# univ_3-1-0-x-rev1.net
KiCad netlist of a schematic drawn in EAGLE
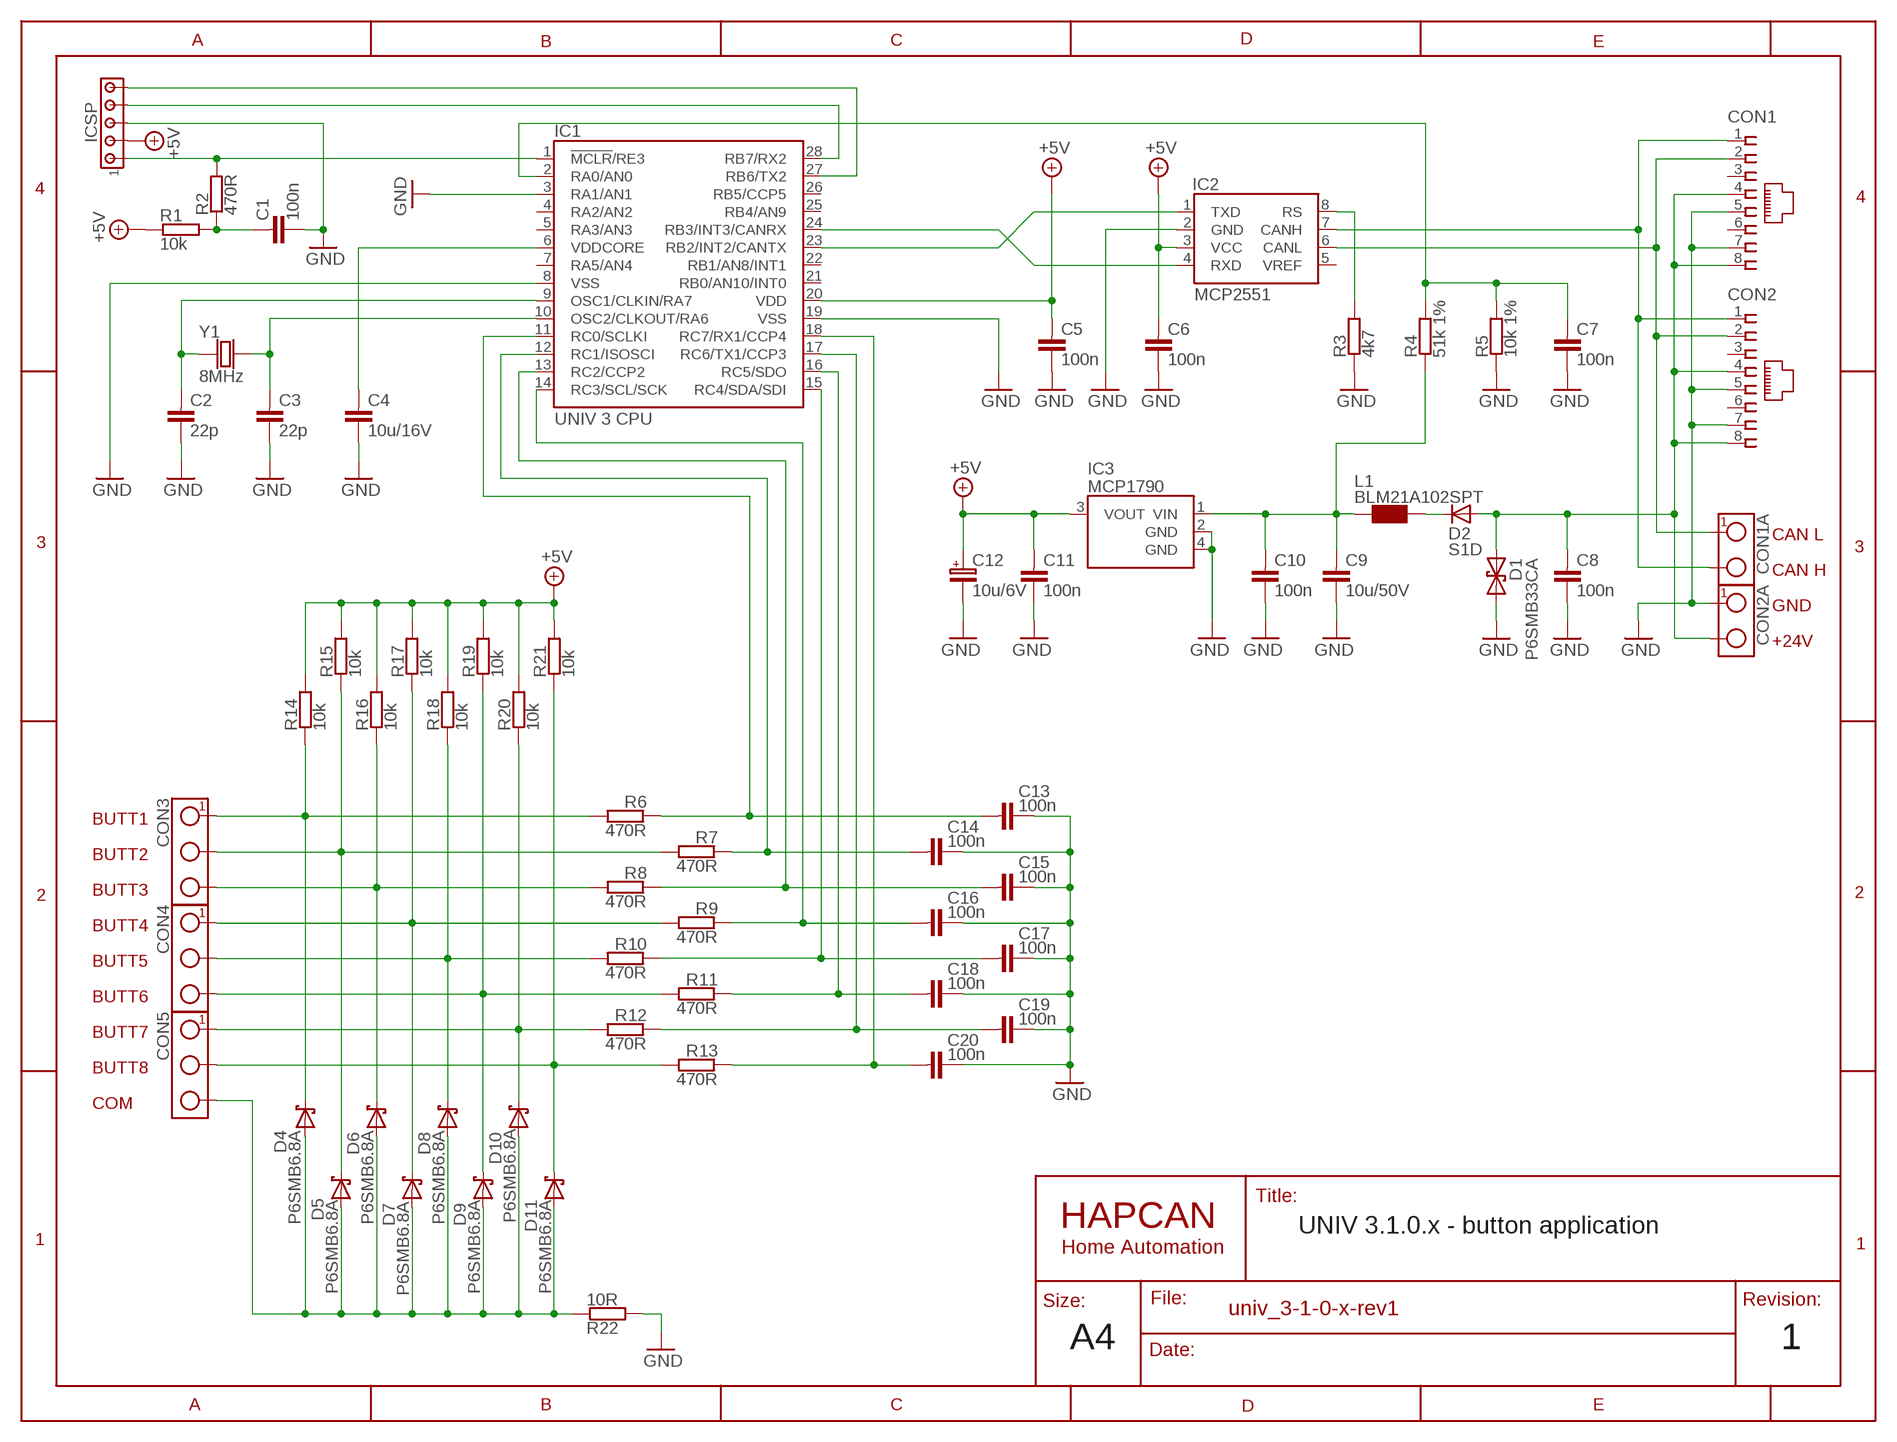
[diagram p0: schematic, sheet 1]

(export (version "E")
  (design (tool "Eeschema 10.0.6"))
  (components
    (comp (ref "C1")
      (value "100n")
      (footprint "eagle-import:0805")
      (libsource (lib "eagle-import") (part "CAPACITOR0805"))
    )
    (comp (ref "C2")
      (value "22p")
      (footprint "eagle-import:0805")
      (libsource (lib "eagle-import") (part "CAPACITOR0805"))
    )
    (comp (ref "C3")
      (value "22p")
      (footprint "eagle-import:0805")
      (libsource (lib "eagle-import") (part "CAPACITOR0805"))
    )
    (comp (ref "C4")
      (value "10u/16V")
      (footprint "eagle-import:0805")
      (libsource (lib "eagle-import") (part "CAPACITOR0805"))
    )
    (comp (ref "C5")
      (value "100n")
      (footprint "eagle-import:0805")
      (libsource (lib "eagle-import") (part "CAPACITOR0805"))
    )
    (comp (ref "C6")
      (value "100n")
      (footprint "eagle-import:0805")
      (libsource (lib "eagle-import") (part "CAPACITOR0805"))
    )
    (comp (ref "C7")
      (value "100n")
      (footprint "eagle-import:0805")
      (libsource (lib "eagle-import") (part "CAPACITOR0805"))
    )
    (comp (ref "C8")
      (value "100n")
      (footprint "eagle-import:0805")
      (libsource (lib "eagle-import") (part "CAPACITOR0805"))
    )
    (comp (ref "C9")
      (value "10u/50V")
      (footprint "eagle-import:1210")
      (libsource (lib "eagle-import") (part "CAPACITOR1210"))
    )
    (comp (ref "C10")
      (value "100n")
      (footprint "eagle-import:0805")
      (libsource (lib "eagle-import") (part "CAPACITOR0805"))
    )
    (comp (ref "C11")
      (value "100n")
      (footprint "eagle-import:0805")
      (libsource (lib "eagle-import") (part "CAPACITOR0805"))
    )
    (comp (ref "C12")
      (value "10u/6V")
      (footprint "eagle-import:SMC_B")
      (libsource (lib "eagle-import") (part "CAPACITOR-POLARIZED-SMC_B"))
    )
    (comp (ref "C13")
      (value "100n")
      (footprint "eagle-import:0805")
      (libsource (lib "eagle-import") (part "CAPACITOR0805"))
    )
    (comp (ref "C14")
      (value "100n")
      (footprint "eagle-import:0805")
      (libsource (lib "eagle-import") (part "CAPACITOR0805"))
    )
    (comp (ref "C15")
      (value "100n")
      (footprint "eagle-import:0805")
      (libsource (lib "eagle-import") (part "CAPACITOR0805"))
    )
    (comp (ref "C16")
      (value "100n")
      (footprint "eagle-import:0805")
      (libsource (lib "eagle-import") (part "CAPACITOR0805"))
    )
    (comp (ref "C17")
      (value "100n")
      (footprint "eagle-import:0805")
      (libsource (lib "eagle-import") (part "CAPACITOR0805"))
    )
    (comp (ref "C18")
      (value "100n")
      (footprint "eagle-import:0805")
      (libsource (lib "eagle-import") (part "CAPACITOR0805"))
    )
    (comp (ref "C19")
      (value "100n")
      (footprint "eagle-import:0805")
      (libsource (lib "eagle-import") (part "CAPACITOR0805"))
    )
    (comp (ref "C20")
      (value "100n")
      (footprint "eagle-import:0805")
      (libsource (lib "eagle-import") (part "CAPACITOR0805"))
    )
    (comp (ref "CON1")
      (value "RJ45-SOCKET")
      (footprint "eagle-import:RJ45-PCB-SOCKET")
      (libsource (lib "eagle-import") (part "RJ45-SOCKET"))
    )
    (comp (ref "CON1A")
      (value "TERMINAL-2")
      (footprint "eagle-import:ARK2-5X10,5MM")
      (libsource (lib "eagle-import") (part "TERMINAL-2-5X10,5MM"))
    )
    (comp (ref "CON2")
      (value "RJ45-SOCKET")
      (footprint "eagle-import:RJ45-PCB-SOCKET")
      (libsource (lib "eagle-import") (part "RJ45-SOCKET"))
    )
    (comp (ref "CON2A")
      (value "TERMINAL-2")
      (footprint "eagle-import:ARK2-5X10,5MM")
      (libsource (lib "eagle-import") (part "TERMINAL-2-5X10,5MM"))
    )
    (comp (ref "CON3")
      (value "TERMINAL-3")
      (footprint "eagle-import:ARK3-5X10.5MM")
      (libsource (lib "eagle-import") (part "TERMINAL-3-5X10.5MM"))
    )
    (comp (ref "CON4")
      (value "TERMINAL-3")
      (footprint "eagle-import:ARK3-5X10.5MM")
      (libsource (lib "eagle-import") (part "TERMINAL-3-5X10.5MM"))
    )
    (comp (ref "CON5")
      (value "TERMINAL-3")
      (footprint "eagle-import:ARK3-5X10.5MM")
      (libsource (lib "eagle-import") (part "TERMINAL-3-5X10.5MM"))
    )
    (comp (ref "D1")
      (value "P6SMB33CA")
      (footprint "eagle-import:DO-214_TRANSIL2")
      (libsource (lib "eagle-import") (part "DIODE_TRANSIL"))
    )
    (comp (ref "D2")
      (value "S1D")
      (footprint "eagle-import:DO-214")
      (libsource (lib "eagle-import") (part "DIODEDO-214"))
    )
    (comp (ref "D4")
      (value "P6SMB6.8A")
      (footprint "eagle-import:DO-214")
      (libsource (lib "eagle-import") (part "DIODE_TRANSIL1"))
    )
    (comp (ref "D5")
      (value "P6SMB6.8A")
      (footprint "eagle-import:DO-214")
      (libsource (lib "eagle-import") (part "DIODE_TRANSIL1"))
    )
    (comp (ref "D6")
      (value "P6SMB6.8A")
      (footprint "eagle-import:DO-214")
      (libsource (lib "eagle-import") (part "DIODE_TRANSIL1"))
    )
    (comp (ref "D7")
      (value "P6SMB6.8A")
      (footprint "eagle-import:DO-214")
      (libsource (lib "eagle-import") (part "DIODE_TRANSIL1"))
    )
    (comp (ref "D8")
      (value "P6SMB6.8A")
      (footprint "eagle-import:DO-214")
      (libsource (lib "eagle-import") (part "DIODE_TRANSIL1"))
    )
    (comp (ref "D9")
      (value "P6SMB6.8A")
      (footprint "eagle-import:DO-214")
      (libsource (lib "eagle-import") (part "DIODE_TRANSIL1"))
    )
    (comp (ref "D10")
      (value "P6SMB6.8A")
      (footprint "eagle-import:DO-214")
      (libsource (lib "eagle-import") (part "DIODE_TRANSIL1"))
    )
    (comp (ref "D11")
      (value "P6SMB6.8A")
      (footprint "eagle-import:DO-214")
      (libsource (lib "eagle-import") (part "DIODE_TRANSIL1"))
    )
    (comp (ref "IC1")
      (value "UNIV 3 CPU")
      (footprint "eagle-import:UNIV3CPU")
      (libsource (lib "eagle-import") (part "UNIV3(CPU)"))
    )
    (comp (ref "IC2")
      (value "MCP2551")
      (footprint "eagle-import:SO-08")
      (libsource (lib "eagle-import") (part "MCP2551"))
    )
    (comp (ref "IC3")
      (value "MCP1790")
      (footprint "eagle-import:SOT-223")
      (libsource (lib "eagle-import") (part "MCP1790"))
    )
    (comp (ref "ICSP")
      (value "HEADER5")
      (footprint "eagle-import:SIP-5")
      (libsource (lib "eagle-import") (part "HEADER5"))
    )
    (comp (ref "L1")
      (value "BLM21A102SPT")
      (footprint "eagle-import:0805")
      (libsource (lib "eagle-import") (part "BLMXXX"))
    )
    (comp (ref "R1")
      (value "10k")
      (footprint "eagle-import:0805")
      (libsource (lib "eagle-import") (part "RESISTOR"))
    )
    (comp (ref "R2")
      (value "470R")
      (footprint "eagle-import:0805")
      (libsource (lib "eagle-import") (part "RESISTOR"))
    )
    (comp (ref "R3")
      (value "4k7")
      (footprint "eagle-import:0805")
      (libsource (lib "eagle-import") (part "RESISTOR"))
    )
    (comp (ref "R4")
      (value "51k 1%")
      (footprint "eagle-import:0805")
      (libsource (lib "eagle-import") (part "RESISTOR"))
    )
    (comp (ref "R5")
      (value "10k 1%")
      (footprint "eagle-import:0805")
      (libsource (lib "eagle-import") (part "RESISTOR"))
    )
    (comp (ref "R6")
      (value "470R")
      (footprint "eagle-import:0805")
      (libsource (lib "eagle-import") (part "RESISTOR"))
    )
    (comp (ref "R7")
      (value "470R")
      (footprint "eagle-import:0805")
      (libsource (lib "eagle-import") (part "RESISTOR"))
    )
    (comp (ref "R8")
      (value "470R")
      (footprint "eagle-import:0805")
      (libsource (lib "eagle-import") (part "RESISTOR"))
    )
    (comp (ref "R9")
      (value "470R")
      (footprint "eagle-import:0805")
      (libsource (lib "eagle-import") (part "RESISTOR"))
    )
    (comp (ref "R10")
      (value "470R")
      (footprint "eagle-import:0805")
      (libsource (lib "eagle-import") (part "RESISTOR"))
    )
    (comp (ref "R11")
      (value "470R")
      (footprint "eagle-import:0805")
      (libsource (lib "eagle-import") (part "RESISTOR"))
    )
    (comp (ref "R12")
      (value "470R")
      (footprint "eagle-import:0805")
      (libsource (lib "eagle-import") (part "RESISTOR"))
    )
    (comp (ref "R13")
      (value "470R")
      (footprint "eagle-import:0805")
      (libsource (lib "eagle-import") (part "RESISTOR"))
    )
    (comp (ref "R14")
      (value "10k")
      (footprint "eagle-import:0805")
      (libsource (lib "eagle-import") (part "RESISTOR"))
    )
    (comp (ref "R15")
      (value "10k")
      (footprint "eagle-import:0805")
      (libsource (lib "eagle-import") (part "RESISTOR"))
    )
    (comp (ref "R16")
      (value "10k")
      (footprint "eagle-import:0805")
      (libsource (lib "eagle-import") (part "RESISTOR"))
    )
    (comp (ref "R17")
      (value "10k")
      (footprint "eagle-import:0805")
      (libsource (lib "eagle-import") (part "RESISTOR"))
    )
    (comp (ref "R18")
      (value "10k")
      (footprint "eagle-import:0805")
      (libsource (lib "eagle-import") (part "RESISTOR"))
    )
    (comp (ref "R19")
      (value "10k")
      (footprint "eagle-import:0805")
      (libsource (lib "eagle-import") (part "RESISTOR"))
    )
    (comp (ref "R20")
      (value "10k")
      (footprint "eagle-import:0805")
      (libsource (lib "eagle-import") (part "RESISTOR"))
    )
    (comp (ref "R21")
      (value "10k")
      (footprint "eagle-import:0805")
      (libsource (lib "eagle-import") (part "RESISTOR"))
    )
    (comp (ref "R22")
      (value "10R")
      (footprint "eagle-import:0805")
      (libsource (lib "eagle-import") (part "RESISTOR"))
    )
    (comp (ref "Y1")
      (value "8MHz")
      (footprint "eagle-import:CRYSTAL-HC49V")
      (libsource (lib "eagle-import") (part "CRYSTALHC49V"))
    )
  )
  (nets
    (net (code "1") (name "+5V") (class "Default")
      (node (ref "C11") (pin "1") (pinfunction "1_1") (pintype "passive"))
      (node (ref "C12") (pin "+") (pinfunction "1_+") (pintype "passive"))
      (node (ref "C5") (pin "1") (pinfunction "1_1") (pintype "passive"))
      (node (ref "C6") (pin "1") (pinfunction "1_1") (pintype "passive"))
      (node (ref "IC1") (pin "20") (pinfunction "VDD_20") (pintype "bidirectional"))
      (node (ref "IC2") (pin "3") (pinfunction "VCC_3") (pintype "bidirectional"))
      (node (ref "IC3") (pin "3") (pinfunction "VOUT_3") (pintype "bidirectional"))
      (node (ref "ICSP") (pin "2") (pinfunction "2_2") (pintype "passive"))
      (node (ref "R1") (pin "1") (pinfunction "1_1") (pintype "passive"))
      (node (ref "R14") (pin "2") (pinfunction "2_2") (pintype "passive"))
      (node (ref "R15") (pin "2") (pinfunction "2_2") (pintype "passive"))
      (node (ref "R16") (pin "2") (pinfunction "2_2") (pintype "passive"))
      (node (ref "R17") (pin "2") (pinfunction "2_2") (pintype "passive"))
      (node (ref "R18") (pin "2") (pinfunction "2_2") (pintype "passive"))
      (node (ref "R19") (pin "2") (pinfunction "2_2") (pintype "passive"))
      (node (ref "R20") (pin "2") (pinfunction "2_2") (pintype "passive"))
      (node (ref "R21") (pin "2") (pinfunction "2_2") (pintype "passive"))
    )
    (net (code "2") (name "GND") (class "Default")
      (node (ref "C1") (pin "2") (pinfunction "2_2") (pintype "passive"))
      (node (ref "C10") (pin "2") (pinfunction "2_2") (pintype "passive"))
      (node (ref "C11") (pin "2") (pinfunction "2_2") (pintype "passive"))
      (node (ref "C12") (pin "-") (pinfunction "2_-") (pintype "passive"))
      (node (ref "C13") (pin "2") (pinfunction "2_2") (pintype "passive"))
      (node (ref "C14") (pin "2") (pinfunction "2_2") (pintype "passive"))
      (node (ref "C15") (pin "2") (pinfunction "2_2") (pintype "passive"))
      (node (ref "C16") (pin "2") (pinfunction "2_2") (pintype "passive"))
      (node (ref "C17") (pin "2") (pinfunction "2_2") (pintype "passive"))
      (node (ref "C18") (pin "2") (pinfunction "2_2") (pintype "passive"))
      (node (ref "C19") (pin "2") (pinfunction "2_2") (pintype "passive"))
      (node (ref "C2") (pin "2") (pinfunction "2_2") (pintype "passive"))
      (node (ref "C20") (pin "2") (pinfunction "2_2") (pintype "passive"))
      (node (ref "C3") (pin "2") (pinfunction "2_2") (pintype "passive"))
      (node (ref "C4") (pin "2") (pinfunction "2_2") (pintype "passive"))
      (node (ref "C5") (pin "2") (pinfunction "2_2") (pintype "passive"))
      (node (ref "C6") (pin "2") (pinfunction "2_2") (pintype "passive"))
      (node (ref "C7") (pin "2") (pinfunction "2_2") (pintype "passive"))
      (node (ref "C8") (pin "2") (pinfunction "2_2") (pintype "passive"))
      (node (ref "C9") (pin "2") (pinfunction "2_2") (pintype "passive"))
      (node (ref "CON1") (pin "5") (pinfunction "5_5") (pintype "passive"))
      (node (ref "CON1") (pin "7") (pinfunction "7_7") (pintype "passive"))
      (node (ref "CON2") (pin "5") (pinfunction "5_5") (pintype "passive"))
      (node (ref "CON2") (pin "7") (pinfunction "7_7") (pintype "passive"))
      (node (ref "CON2A") (pin "1") (pinfunction "1_1") (pintype "passive"))
      (node (ref "D1") (pin "C") (pinfunction "2_C") (pintype "passive"))
      (node (ref "IC1") (pin "19") (pinfunction "VSS_19") (pintype "bidirectional"))
      (node (ref "IC1") (pin "3") (pinfunction "RA1/AN1_3") (pintype "bidirectional"))
      (node (ref "IC1") (pin "8") (pinfunction "VSS_8") (pintype "bidirectional"))
      (node (ref "IC2") (pin "2") (pinfunction "GND_2") (pintype "bidirectional"))
      (node (ref "IC3") (pin "2") (pinfunction "GND_2") (pintype "bidirectional"))
      (node (ref "IC3") (pin "4") (pinfunction "GND_4") (pintype "bidirectional"))
      (node (ref "ICSP") (pin "3") (pinfunction "3_3") (pintype "passive"))
      (node (ref "R22") (pin "2") (pinfunction "2_2") (pintype "passive"))
      (node (ref "R3") (pin "1") (pinfunction "1_1") (pintype "passive"))
      (node (ref "R5") (pin "1") (pinfunction "1_1") (pintype "passive"))
    )
    (net (code "3") (name "Net-(C1-Pad1)") (class "Default")
      (node (ref "C1") (pin "1") (pinfunction "1_1") (pintype "passive"))
      (node (ref "R1") (pin "2") (pinfunction "2_2") (pintype "passive"))
      (node (ref "R2") (pin "1") (pinfunction "1_1") (pintype "passive"))
    )
    (net (code "4") (name "Net-(D1-1)") (class "Default")
      (node (ref "C8") (pin "1") (pinfunction "1_1") (pintype "passive"))
      (node (ref "CON1") (pin "4") (pinfunction "4_4") (pintype "passive"))
      (node (ref "CON1") (pin "8") (pinfunction "8_8") (pintype "passive"))
      (node (ref "CON2") (pin "4") (pinfunction "4_4") (pintype "passive"))
      (node (ref "CON2") (pin "8") (pinfunction "8_8") (pintype "passive"))
      (node (ref "CON2A") (pin "2") (pinfunction "2_2") (pintype "passive"))
      (node (ref "D1") (pin "A") (pinfunction "1_A") (pintype "passive"))
      (node (ref "D2") (pin "A") (pinfunction "2_A") (pintype "passive"))
    )
    (net (code "5") (name "Net-(D2-1)") (class "Default")
      (node (ref "D2") (pin "C") (pinfunction "1_C") (pintype "passive"))
      (node (ref "L1") (pin "2") (pinfunction "2_2") (pintype "passive"))
    )
    (net (code "6") (name "Net-(D4-1)") (class "Default")
      (node (ref "CON3") (pin "1") (pinfunction "1_1") (pintype "passive"))
      (node (ref "D4") (pin "C") (pinfunction "1_C") (pintype "passive"))
      (node (ref "R14") (pin "1") (pinfunction "1_1") (pintype "passive"))
      (node (ref "R6") (pin "2") (pinfunction "2_2") (pintype "passive"))
    )
    (net (code "7") (name "Net-(D5-1)") (class "Default")
      (node (ref "CON3") (pin "2") (pinfunction "2_2") (pintype "passive"))
      (node (ref "D5") (pin "C") (pinfunction "1_C") (pintype "passive"))
      (node (ref "R15") (pin "1") (pinfunction "1_1") (pintype "passive"))
      (node (ref "R7") (pin "2") (pinfunction "2_2") (pintype "passive"))
    )
    (net (code "8") (name "Net-(D6-1)") (class "Default")
      (node (ref "CON3") (pin "3") (pinfunction "3_3") (pintype "passive"))
      (node (ref "D6") (pin "C") (pinfunction "1_C") (pintype "passive"))
      (node (ref "R16") (pin "1") (pinfunction "1_1") (pintype "passive"))
      (node (ref "R8") (pin "2") (pinfunction "2_2") (pintype "passive"))
    )
    (net (code "9") (name "Net-(D7-1)") (class "Default")
      (node (ref "CON4") (pin "1") (pinfunction "1_1") (pintype "passive"))
      (node (ref "D7") (pin "C") (pinfunction "1_C") (pintype "passive"))
      (node (ref "R17") (pin "1") (pinfunction "1_1") (pintype "passive"))
      (node (ref "R9") (pin "2") (pinfunction "2_2") (pintype "passive"))
    )
    (net (code "10") (name "Net-(D8-1)") (class "Default")
      (node (ref "CON4") (pin "2") (pinfunction "2_2") (pintype "passive"))
      (node (ref "D8") (pin "C") (pinfunction "1_C") (pintype "passive"))
      (node (ref "R10") (pin "2") (pinfunction "2_2") (pintype "passive"))
      (node (ref "R18") (pin "1") (pinfunction "1_1") (pintype "passive"))
    )
    (net (code "11") (name "Net-(D9-1)") (class "Default")
      (node (ref "CON4") (pin "3") (pinfunction "3_3") (pintype "passive"))
      (node (ref "D9") (pin "C") (pinfunction "1_C") (pintype "passive"))
      (node (ref "R11") (pin "2") (pinfunction "2_2") (pintype "passive"))
      (node (ref "R19") (pin "1") (pinfunction "1_1") (pintype "passive"))
    )
    (net (code "12") (name "Net-(D10-1)") (class "Default")
      (node (ref "CON5") (pin "1") (pinfunction "1_1") (pintype "passive"))
      (node (ref "D10") (pin "C") (pinfunction "1_C") (pintype "passive"))
      (node (ref "R12") (pin "2") (pinfunction "2_2") (pintype "passive"))
      (node (ref "R20") (pin "1") (pinfunction "1_1") (pintype "passive"))
    )
    (net (code "13") (name "Net-(D10-2)") (class "Default")
      (node (ref "CON5") (pin "3") (pinfunction "3_3") (pintype "passive"))
      (node (ref "D10") (pin "A") (pinfunction "2_A") (pintype "passive"))
      (node (ref "D11") (pin "A") (pinfunction "2_A") (pintype "passive"))
      (node (ref "D4") (pin "A") (pinfunction "2_A") (pintype "passive"))
      (node (ref "D5") (pin "A") (pinfunction "2_A") (pintype "passive"))
      (node (ref "D6") (pin "A") (pinfunction "2_A") (pintype "passive"))
      (node (ref "D7") (pin "A") (pinfunction "2_A") (pintype "passive"))
      (node (ref "D8") (pin "A") (pinfunction "2_A") (pintype "passive"))
      (node (ref "D9") (pin "A") (pinfunction "2_A") (pintype "passive"))
      (node (ref "R22") (pin "1") (pinfunction "1_1") (pintype "passive"))
    )
    (net (code "14") (name "Net-(D11-1)") (class "Default")
      (node (ref "CON5") (pin "2") (pinfunction "2_2") (pintype "passive"))
      (node (ref "D11") (pin "C") (pinfunction "1_C") (pintype "passive"))
      (node (ref "R13") (pin "2") (pinfunction "2_2") (pintype "passive"))
      (node (ref "R21") (pin "1") (pinfunction "1_1") (pintype "passive"))
    )
    (net (code "15") (name "Net-(IC1-OSC1{slash}CLKIN{slash}RA7)") (class "Default")
      (node (ref "C2") (pin "1") (pinfunction "1_1") (pintype "passive"))
      (node (ref "IC1") (pin "9") (pinfunction "OSC1/CLKIN/RA7_9") (pintype "bidirectional"))
      (node (ref "Y1") (pin "1") (pinfunction "1_1") (pintype "passive"))
    )
    (net (code "16") (name "Net-(IC1-OSC2{slash}CLKOUT{slash}RA6)") (class "Default")
      (node (ref "C3") (pin "1") (pinfunction "1_1") (pintype "passive"))
      (node (ref "IC1") (pin "10") (pinfunction "OSC2/CLKOUT/RA6_10") (pintype "bidirectional"))
      (node (ref "Y1") (pin "2") (pinfunction "2_2") (pintype "passive"))
    )
    (net (code "17") (name "Net-(IC1-RA0{slash}AN0)") (class "Default")
      (node (ref "C7") (pin "1") (pinfunction "1_1") (pintype "passive"))
      (node (ref "IC1") (pin "2") (pinfunction "RA0/AN0_2") (pintype "bidirectional"))
      (node (ref "R4") (pin "2") (pinfunction "2_2") (pintype "passive"))
      (node (ref "R5") (pin "2") (pinfunction "2_2") (pintype "passive"))
    )
    (net (code "18") (name "Net-(IC1-RB2{slash}INT2{slash}CANTX)") (class "Default")
      (node (ref "IC1") (pin "23") (pinfunction "RB2/INT2/CANTX_23") (pintype "bidirectional"))
      (node (ref "IC2") (pin "1") (pinfunction "TXD_1") (pintype "bidirectional"))
    )
    (net (code "19") (name "Net-(IC1-RB3{slash}INT3{slash}CANRX)") (class "Default")
      (node (ref "IC1") (pin "24") (pinfunction "RB3/INT3/CANRX_24") (pintype "bidirectional"))
      (node (ref "IC2") (pin "4") (pinfunction "RXD_4") (pintype "bidirectional"))
    )
    (net (code "20") (name "Net-(IC1-RB6{slash}TX2)") (class "Default")
      (node (ref "IC1") (pin "27") (pinfunction "RB6/TX2_27") (pintype "bidirectional"))
      (node (ref "ICSP") (pin "5") (pinfunction "5_5") (pintype "passive"))
    )
    (net (code "21") (name "Net-(IC1-RB7{slash}RX2)") (class "Default")
      (node (ref "IC1") (pin "28") (pinfunction "RB7/RX2_28") (pintype "bidirectional"))
      (node (ref "ICSP") (pin "4") (pinfunction "4_4") (pintype "passive"))
    )
    (net (code "22") (name "Net-(IC1-RC0{slash}SCLKI)") (class "Default")
      (node (ref "C13") (pin "1") (pinfunction "1_1") (pintype "passive"))
      (node (ref "IC1") (pin "11") (pinfunction "RC0/SCLKI_11") (pintype "bidirectional"))
      (node (ref "R6") (pin "1") (pinfunction "1_1") (pintype "passive"))
    )
    (net (code "23") (name "Net-(IC1-RC1{slash}ISOSCI)") (class "Default")
      (node (ref "C14") (pin "1") (pinfunction "1_1") (pintype "passive"))
      (node (ref "IC1") (pin "12") (pinfunction "RC1/ISOSCI_12") (pintype "bidirectional"))
      (node (ref "R7") (pin "1") (pinfunction "1_1") (pintype "passive"))
    )
    (net (code "24") (name "Net-(IC1-RC2{slash}CCP2)") (class "Default")
      (node (ref "C15") (pin "1") (pinfunction "1_1") (pintype "passive"))
      (node (ref "IC1") (pin "13") (pinfunction "RC2/CCP2_13") (pintype "bidirectional"))
      (node (ref "R8") (pin "1") (pinfunction "1_1") (pintype "passive"))
    )
    (net (code "25") (name "Net-(IC1-RC3{slash}SCL{slash}SCK)") (class "Default")
      (node (ref "C16") (pin "1") (pinfunction "1_1") (pintype "passive"))
      (node (ref "IC1") (pin "14") (pinfunction "RC3/SCL/SCK_14") (pintype "bidirectional"))
      (node (ref "R9") (pin "1") (pinfunction "1_1") (pintype "passive"))
    )
    (net (code "26") (name "Net-(IC1-RC4{slash}SDA{slash}SDI)") (class "Default")
      (node (ref "C17") (pin "1") (pinfunction "1_1") (pintype "passive"))
      (node (ref "IC1") (pin "15") (pinfunction "RC4/SDA/SDI_15") (pintype "bidirectional"))
      (node (ref "R10") (pin "1") (pinfunction "1_1") (pintype "passive"))
    )
    (net (code "27") (name "Net-(IC1-RC5{slash}SDO)") (class "Default")
      (node (ref "C18") (pin "1") (pinfunction "1_1") (pintype "passive"))
      (node (ref "IC1") (pin "16") (pinfunction "RC5/SDO_16") (pintype "bidirectional"))
      (node (ref "R11") (pin "1") (pinfunction "1_1") (pintype "passive"))
    )
    (net (code "28") (name "Net-(IC1-RC6{slash}TX1{slash}CCP3)") (class "Default")
      (node (ref "C19") (pin "1") (pinfunction "1_1") (pintype "passive"))
      (node (ref "IC1") (pin "17") (pinfunction "RC6/TX1/CCP3_17") (pintype "bidirectional"))
      (node (ref "R12") (pin "1") (pinfunction "1_1") (pintype "passive"))
    )
    (net (code "29") (name "Net-(IC1-RC7{slash}RX1{slash}CCP4)") (class "Default")
      (node (ref "C20") (pin "1") (pinfunction "1_1") (pintype "passive"))
      (node (ref "IC1") (pin "18") (pinfunction "RC7/RX1/CCP4_18") (pintype "bidirectional"))
      (node (ref "R13") (pin "1") (pinfunction "1_1") (pintype "passive"))
    )
    (net (code "30") (name "Net-(IC1-VDDCORE)") (class "Default")
      (node (ref "C4") (pin "1") (pinfunction "1_1") (pintype "passive"))
      (node (ref "IC1") (pin "6") (pinfunction "VDDCORE_6") (pintype "bidirectional"))
    )
    (net (code "31") (name "Net-(IC1-~{MCLR}{slash}RE3)") (class "Default")
      (node (ref "IC1") (pin "1") (pinfunction "~{MCLR}/RE3_1") (pintype "bidirectional"))
      (node (ref "ICSP") (pin "1") (pinfunction "1_1") (pintype "passive"))
      (node (ref "R2") (pin "2") (pinfunction "2_2") (pintype "passive"))
    )
    (net (code "32") (name "Net-(IC2-CANH)") (class "Default")
      (node (ref "CON1") (pin "1") (pinfunction "1_1") (pintype "passive"))
      (node (ref "CON1A") (pin "2") (pinfunction "2_2") (pintype "passive"))
      (node (ref "CON2") (pin "1") (pinfunction "1_1") (pintype "passive"))
      (node (ref "IC2") (pin "7") (pinfunction "CANH_7") (pintype "bidirectional"))
    )
    (net (code "33") (name "Net-(IC2-CANL)") (class "Default")
      (node (ref "CON1") (pin "2") (pinfunction "2_2") (pintype "passive"))
      (node (ref "CON1A") (pin "1") (pinfunction "1_1") (pintype "passive"))
      (node (ref "CON2") (pin "2") (pinfunction "2_2") (pintype "passive"))
      (node (ref "IC2") (pin "6") (pinfunction "CANL_6") (pintype "bidirectional"))
    )
    (net (code "34") (name "Net-(IC2-RS)") (class "Default")
      (node (ref "IC2") (pin "8") (pinfunction "RS_8") (pintype "bidirectional"))
      (node (ref "R3") (pin "2") (pinfunction "2_2") (pintype "passive"))
    )
    (net (code "35") (name "Net-(IC3-VIN)") (class "Default")
      (node (ref "C10") (pin "1") (pinfunction "1_1") (pintype "passive"))
      (node (ref "C9") (pin "1") (pinfunction "1_1") (pintype "passive"))
      (node (ref "IC3") (pin "1") (pinfunction "VIN_1") (pintype "bidirectional"))
      (node (ref "L1") (pin "1") (pinfunction "1_1") (pintype "passive"))
      (node (ref "R4") (pin "1") (pinfunction "1_1") (pintype "passive"))
    )
    (net (code "36") (name "unconnected-(CON1-Pad3)") (class "Default")
      (node (ref "CON1") (pin "3") (pinfunction "3_3") (pintype "passive"))
    )
    (net (code "37") (name "unconnected-(CON1-Pad6)") (class "Default")
      (node (ref "CON1") (pin "6") (pinfunction "6_6") (pintype "passive"))
    )
    (net (code "38") (name "unconnected-(CON2-Pad3)") (class "Default")
      (node (ref "CON2") (pin "3") (pinfunction "3_3") (pintype "passive"))
    )
    (net (code "39") (name "unconnected-(CON2-Pad6)") (class "Default")
      (node (ref "CON2") (pin "6") (pinfunction "6_6") (pintype "passive"))
    )
    (net (code "40") (name "unconnected-(IC1-RA2{slash}AN2-Pad4)") (class "Default")
      (node (ref "IC1") (pin "4") (pinfunction "RA2/AN2_4") (pintype "bidirectional"))
    )
    (net (code "41") (name "unconnected-(IC1-RA3{slash}AN3-Pad5)") (class "Default")
      (node (ref "IC1") (pin "5") (pinfunction "RA3/AN3_5") (pintype "bidirectional"))
    )
    (net (code "42") (name "unconnected-(IC1-RA5{slash}AN4-Pad7)") (class "Default")
      (node (ref "IC1") (pin "7") (pinfunction "RA5/AN4_7") (pintype "bidirectional"))
    )
    (net (code "43") (name "unconnected-(IC1-RB0{slash}AN10{slash}INT0-Pad21)") (class "Default")
      (node (ref "IC1") (pin "21") (pinfunction "RB0/AN10/INT0_21") (pintype "bidirectional"))
    )
    (net (code "44") (name "unconnected-(IC1-RB1{slash}AN8{slash}INT1-Pad22)") (class "Default")
      (node (ref "IC1") (pin "22") (pinfunction "RB1/AN8/INT1_22") (pintype "bidirectional"))
    )
    (net (code "45") (name "unconnected-(IC1-RB4{slash}AN9-Pad25)") (class "Default")
      (node (ref "IC1") (pin "25") (pinfunction "RB4/AN9_25") (pintype "bidirectional"))
    )
    (net (code "46") (name "unconnected-(IC1-RB5{slash}CCP5-Pad26)") (class "Default")
      (node (ref "IC1") (pin "26") (pinfunction "RB5/CCP5_26") (pintype "bidirectional"))
    )
    (net (code "47") (name "unconnected-(IC2-VREF-Pad5)") (class "Default")
      (node (ref "IC2") (pin "5") (pinfunction "VREF_5") (pintype "bidirectional"))
    )
  )
)
